# CF_DAC.net
KiCad netlist of a schematic drawn in Altium Designer
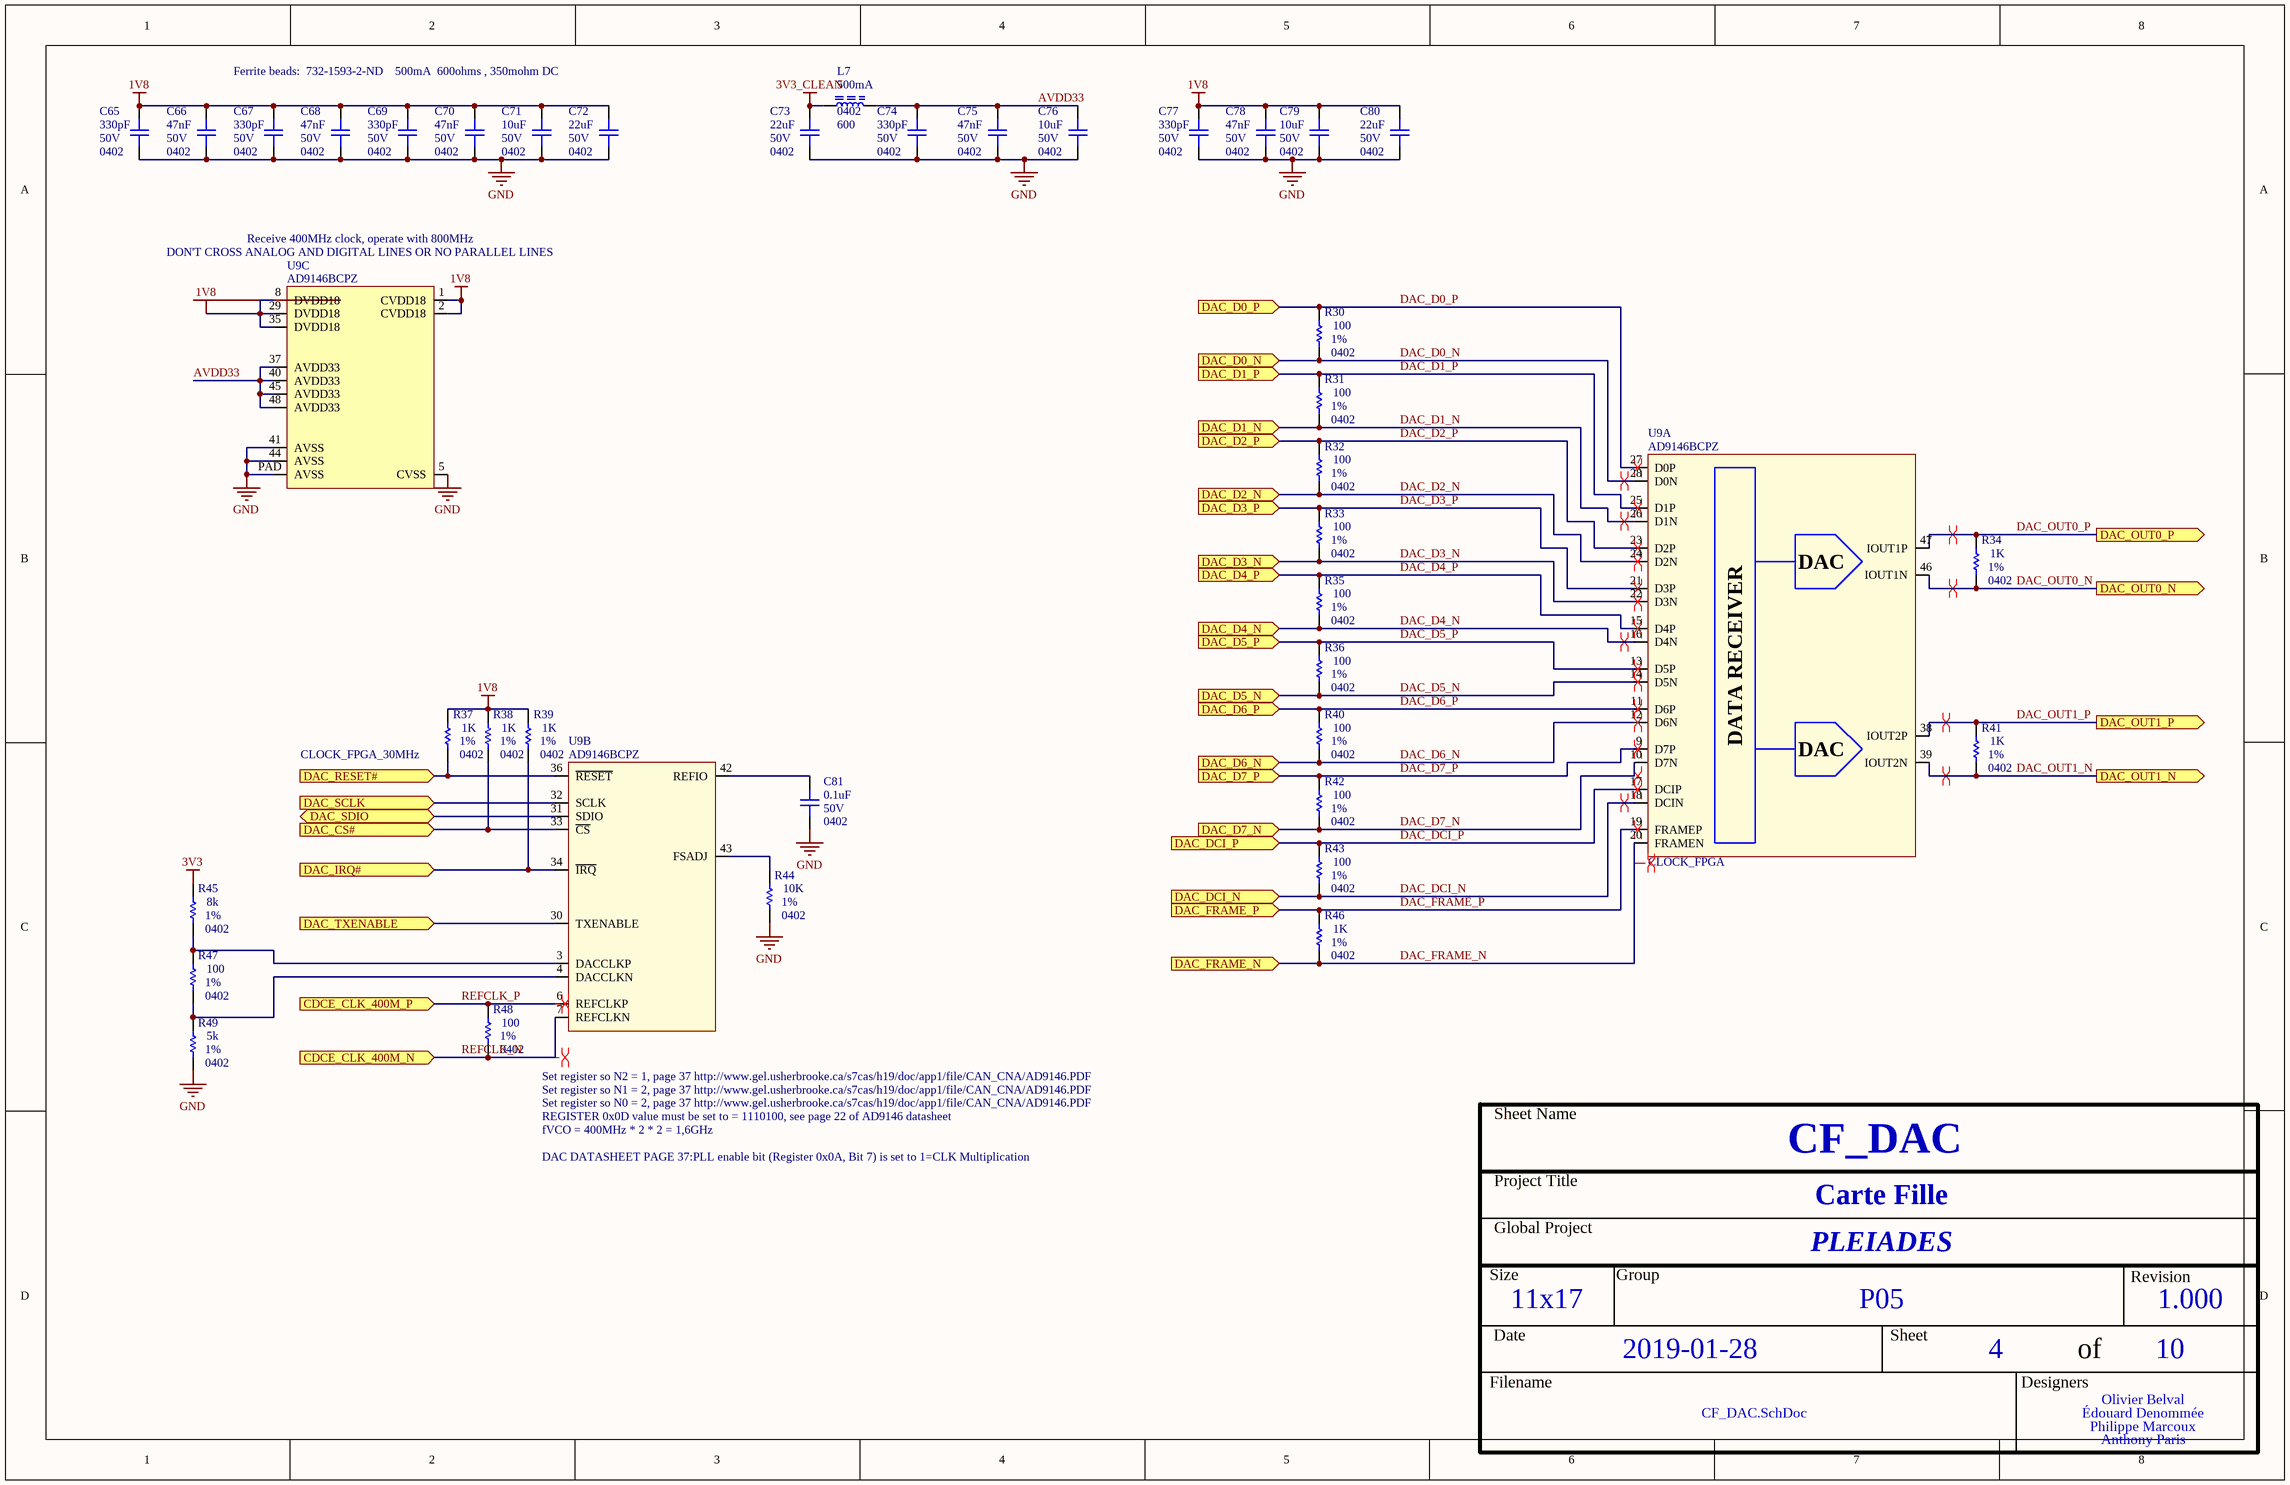
[diagram p0: CF_DAC.SchDoc]

(export (version "E")
  (design (tool "Eeschema 10.0.6"))
  (components
    (comp (ref "C65")
      (value "330pF")
      (footprint "CAP_0402")
      (description "CAP - 0402")
      (fields
        (field (name "VOLTAGE") "50V")
        (field (name "PACKAGE") "0402")
        (field (name "CREATEDBY") "Jonathan Bouchard")
      )
      (libsource (lib "S7CAS_Lib2019_REV1_00") (part "CAP - 0402"))
    )
    (comp (ref "C66")
      (value "47nF")
      (footprint "CAP_0402")
      (description "CAP - 0402")
      (fields
        (field (name "VOLTAGE") "50V")
        (field (name "PACKAGE") "0402")
        (field (name "CREATEDBY") "Jonathan Bouchard")
      )
      (libsource (lib "S7CAS_Lib2019_REV1_00") (part "CAP - 0402"))
    )
    (comp (ref "C67")
      (value "330pF")
      (footprint "CAP_0402")
      (description "CAP - 0402")
      (fields
        (field (name "VOLTAGE") "50V")
        (field (name "PACKAGE") "0402")
        (field (name "CREATEDBY") "Jonathan Bouchard")
      )
      (libsource (lib "S7CAS_Lib2019_REV1_00") (part "CAP - 0402"))
    )
    (comp (ref "C68")
      (value "47nF")
      (footprint "CAP_0402")
      (description "CAP - 0402")
      (fields
        (field (name "VOLTAGE") "50V")
        (field (name "PACKAGE") "0402")
        (field (name "CREATEDBY") "Jonathan Bouchard")
      )
      (libsource (lib "S7CAS_Lib2019_REV1_00") (part "CAP - 0402"))
    )
    (comp (ref "C69")
      (value "330pF")
      (footprint "CAP_0402")
      (description "CAP - 0402")
      (fields
        (field (name "VOLTAGE") "50V")
        (field (name "PACKAGE") "0402")
        (field (name "CREATEDBY") "Jonathan Bouchard")
      )
      (libsource (lib "S7CAS_Lib2019_REV1_00") (part "CAP - 0402"))
    )
    (comp (ref "C70")
      (value "47nF")
      (footprint "CAP_0402")
      (description "CAP - 0402")
      (fields
        (field (name "VOLTAGE") "50V")
        (field (name "PACKAGE") "0402")
        (field (name "CREATEDBY") "Jonathan Bouchard")
      )
      (libsource (lib "S7CAS_Lib2019_REV1_00") (part "CAP - 0402"))
    )
    (comp (ref "C71")
      (value "10uF")
      (footprint "CAP_0402")
      (description "CAP - 0402")
      (fields
        (field (name "VOLTAGE") "50V")
        (field (name "PACKAGE") "0402")
        (field (name "CREATEDBY") "Jonathan Bouchard")
      )
      (libsource (lib "S7CAS_Lib2019_REV1_00") (part "CAP - 0402"))
    )
    (comp (ref "C72")
      (value "22uF")
      (footprint "CAP_0402")
      (description "CAP - 0402")
      (fields
        (field (name "VOLTAGE") "50V")
        (field (name "PACKAGE") "0402")
        (field (name "CREATEDBY") "Jonathan Bouchard")
      )
      (libsource (lib "S7CAS_Lib2019_REV1_00") (part "CAP - 0402"))
    )
    (comp (ref "C73")
      (value "22uF")
      (footprint "CAP_0402")
      (description "CAP - 0402")
      (fields
        (field (name "VOLTAGE") "50V")
        (field (name "PACKAGE") "0402")
        (field (name "CREATEDBY") "Jonathan Bouchard")
      )
      (libsource (lib "S7CAS_Lib2019_REV1_00") (part "CAP - 0402"))
    )
    (comp (ref "C74")
      (value "330pF")
      (footprint "CAP_0402")
      (description "CAP - 0402")
      (fields
        (field (name "VOLTAGE") "50V")
        (field (name "PACKAGE") "0402")
        (field (name "CREATEDBY") "Jonathan Bouchard")
      )
      (libsource (lib "S7CAS_Lib2019_REV1_00") (part "CAP - 0402"))
    )
    (comp (ref "C75")
      (value "47nF")
      (footprint "CAP_0402")
      (description "CAP - 0402")
      (fields
        (field (name "VOLTAGE") "50V")
        (field (name "PACKAGE") "0402")
        (field (name "CREATEDBY") "Jonathan Bouchard")
      )
      (libsource (lib "S7CAS_Lib2019_REV1_00") (part "CAP - 0402"))
    )
    (comp (ref "C76")
      (value "10uF")
      (footprint "CAP_0402")
      (description "CAP - 0402")
      (fields
        (field (name "VOLTAGE") "50V")
        (field (name "PACKAGE") "0402")
        (field (name "CREATEDBY") "Jonathan Bouchard")
      )
      (libsource (lib "S7CAS_Lib2019_REV1_00") (part "CAP - 0402"))
    )
    (comp (ref "C77")
      (value "330pF")
      (footprint "CAP_0402")
      (description "CAP - 0402")
      (fields
        (field (name "VOLTAGE") "50V")
        (field (name "PACKAGE") "0402")
        (field (name "CREATEDBY") "Jonathan Bouchard")
      )
      (libsource (lib "S7CAS_Lib2019_REV1_00") (part "CAP - 0402"))
    )
    (comp (ref "C78")
      (value "47nF")
      (footprint "CAP_0402")
      (description "CAP - 0402")
      (fields
        (field (name "VOLTAGE") "50V")
        (field (name "PACKAGE") "0402")
        (field (name "CREATEDBY") "Jonathan Bouchard")
      )
      (libsource (lib "S7CAS_Lib2019_REV1_00") (part "CAP - 0402"))
    )
    (comp (ref "C79")
      (value "10uF")
      (footprint "CAP_0402")
      (description "CAP - 0402")
      (fields
        (field (name "VOLTAGE") "50V")
        (field (name "PACKAGE") "0402")
        (field (name "CREATEDBY") "Jonathan Bouchard")
      )
      (libsource (lib "S7CAS_Lib2019_REV1_00") (part "CAP - 0402"))
    )
    (comp (ref "C80")
      (value "22uF")
      (footprint "CAP_0402")
      (description "CAP - 0402")
      (fields
        (field (name "VOLTAGE") "50V")
        (field (name "PACKAGE") "0402")
        (field (name "CREATEDBY") "Jonathan Bouchard")
      )
      (libsource (lib "S7CAS_Lib2019_REV1_00") (part "CAP - 0402"))
    )
    (comp (ref "C81")
      (value "0.1uF")
      (footprint "CAP_0402")
      (description "CAP - 0402")
      (fields
        (field (name "VOLTAGE") "50V")
        (field (name "PACKAGE") "0402")
        (field (name "CREATEDBY") "Jonathan Bouchard")
      )
      (libsource (lib "S7CAS_Lib2019_REV1_00") (part "CAP - 0402"))
    )
    (comp (ref "L7")
      (value "600")
      (footprint "FER_0402")
      (description "FER - 0402")
      (fields
        (field (name "CURRENT") "500mA")
        (field (name "PACKAGE") "0402")
        (field (name "CREATEDBY") "Jonathan Bouchard")
      )
      (libsource (lib "S7CAS_Lib2019_REV1_00") (part "FER - 0402"))
    )
    (comp (ref "R30")
      (value "100")
      (footprint "RES_0402")
      (description "RES - 0402")
      (fields
        (field (name "VOLTAGE") "50V")
        (field (name "POWER") "1/16W")
        (field (name "PACKAGE") "0402")
        (field (name "PRECISION") "1%")
        (field (name "CREATEDBY") "Jonathan Bouchard")
      )
      (libsource (lib "S7CAS_Lib2019_REV1_00") (part "RES - 0402"))
    )
    (comp (ref "R31")
      (value "100")
      (footprint "RES_0402")
      (description "RES - 0402")
      (fields
        (field (name "VOLTAGE") "50V")
        (field (name "POWER") "1/16W")
        (field (name "PACKAGE") "0402")
        (field (name "PRECISION") "1%")
        (field (name "CREATEDBY") "Jonathan Bouchard")
      )
      (libsource (lib "S7CAS_Lib2019_REV1_00") (part "RES - 0402"))
    )
    (comp (ref "R32")
      (value "100")
      (footprint "RES_0402")
      (description "RES - 0402")
      (fields
        (field (name "VOLTAGE") "50V")
        (field (name "POWER") "1/16W")
        (field (name "PACKAGE") "0402")
        (field (name "PRECISION") "1%")
        (field (name "CREATEDBY") "Jonathan Bouchard")
      )
      (libsource (lib "S7CAS_Lib2019_REV1_00") (part "RES - 0402"))
    )
    (comp (ref "R33")
      (value "100")
      (footprint "RES_0402")
      (description "RES - 0402")
      (fields
        (field (name "VOLTAGE") "50V")
        (field (name "POWER") "1/16W")
        (field (name "PACKAGE") "0402")
        (field (name "PRECISION") "1%")
        (field (name "CREATEDBY") "Jonathan Bouchard")
      )
      (libsource (lib "S7CAS_Lib2019_REV1_00") (part "RES - 0402"))
    )
    (comp (ref "R34")
      (value "1K")
      (footprint "RES_0402")
      (description "RES - 0402")
      (fields
        (field (name "VOLTAGE") "50V")
        (field (name "POWER") "1/16W")
        (field (name "PACKAGE") "0402")
        (field (name "PRECISION") "1%")
        (field (name "CREATEDBY") "Jonathan Bouchard")
      )
      (libsource (lib "S7CAS_Lib2019_REV1_00") (part "RES - 0402"))
    )
    (comp (ref "R35")
      (value "100")
      (footprint "RES_0402")
      (description "RES - 0402")
      (fields
        (field (name "VOLTAGE") "50V")
        (field (name "POWER") "1/16W")
        (field (name "PACKAGE") "0402")
        (field (name "PRECISION") "1%")
        (field (name "CREATEDBY") "Jonathan Bouchard")
      )
      (libsource (lib "S7CAS_Lib2019_REV1_00") (part "RES - 0402"))
    )
    (comp (ref "R36")
      (value "100")
      (footprint "RES_0402")
      (description "RES - 0402")
      (fields
        (field (name "VOLTAGE") "50V")
        (field (name "POWER") "1/16W")
        (field (name "PACKAGE") "0402")
        (field (name "PRECISION") "1%")
        (field (name "CREATEDBY") "Jonathan Bouchard")
      )
      (libsource (lib "S7CAS_Lib2019_REV1_00") (part "RES - 0402"))
    )
    (comp (ref "R37")
      (value "1K")
      (footprint "RES_0402")
      (description "RES - 0402")
      (fields
        (field (name "VOLTAGE") "50V")
        (field (name "POWER") "1/16W")
        (field (name "PACKAGE") "0402")
        (field (name "PRECISION") "1%")
        (field (name "CREATEDBY") "Jonathan Bouchard")
      )
      (libsource (lib "S7CAS_Lib2019_REV1_00") (part "RES - 0402"))
    )
    (comp (ref "R38")
      (value "1K")
      (footprint "RES_0402")
      (description "RES - 0402")
      (fields
        (field (name "VOLTAGE") "50V")
        (field (name "POWER") "1/16W")
        (field (name "PACKAGE") "0402")
        (field (name "PRECISION") "1%")
        (field (name "CREATEDBY") "Jonathan Bouchard")
      )
      (libsource (lib "S7CAS_Lib2019_REV1_00") (part "RES - 0402"))
    )
    (comp (ref "R39")
      (value "1K")
      (footprint "RES_0402")
      (description "RES - 0402")
      (fields
        (field (name "VOLTAGE") "50V")
        (field (name "POWER") "1/16W")
        (field (name "PACKAGE") "0402")
        (field (name "PRECISION") "1%")
        (field (name "CREATEDBY") "Jonathan Bouchard")
      )
      (libsource (lib "S7CAS_Lib2019_REV1_00") (part "RES - 0402"))
    )
    (comp (ref "R40")
      (value "100")
      (footprint "RES_0402")
      (description "RES - 0402")
      (fields
        (field (name "VOLTAGE") "50V")
        (field (name "POWER") "1/16W")
        (field (name "PACKAGE") "0402")
        (field (name "PRECISION") "1%")
        (field (name "CREATEDBY") "Jonathan Bouchard")
      )
      (libsource (lib "S7CAS_Lib2019_REV1_00") (part "RES - 0402"))
    )
    (comp (ref "R41")
      (value "1K")
      (footprint "RES_0402")
      (description "RES - 0402")
      (fields
        (field (name "VOLTAGE") "50V")
        (field (name "POWER") "1/16W")
        (field (name "PACKAGE") "0402")
        (field (name "PRECISION") "1%")
        (field (name "CREATEDBY") "Jonathan Bouchard")
      )
      (libsource (lib "S7CAS_Lib2019_REV1_00") (part "RES - 0402"))
    )
    (comp (ref "R42")
      (value "100")
      (footprint "RES_0402")
      (description "RES - 0402")
      (fields
        (field (name "VOLTAGE") "50V")
        (field (name "POWER") "1/16W")
        (field (name "PACKAGE") "0402")
        (field (name "PRECISION") "1%")
        (field (name "CREATEDBY") "Jonathan Bouchard")
      )
      (libsource (lib "S7CAS_Lib2019_REV1_00") (part "RES - 0402"))
    )
    (comp (ref "R43")
      (value "100")
      (footprint "RES_0402")
      (description "RES - 0402")
      (fields
        (field (name "VOLTAGE") "50V")
        (field (name "POWER") "1/16W")
        (field (name "PACKAGE") "0402")
        (field (name "PRECISION") "1%")
        (field (name "CREATEDBY") "Jonathan Bouchard")
      )
      (libsource (lib "S7CAS_Lib2019_REV1_00") (part "RES - 0402"))
    )
    (comp (ref "R44")
      (value "10K")
      (footprint "RES_0402")
      (description "RES - 0402")
      (fields
        (field (name "VOLTAGE") "50V")
        (field (name "POWER") "1/16W")
        (field (name "PACKAGE") "0402")
        (field (name "PRECISION") "1%")
        (field (name "CREATEDBY") "Jonathan Bouchard")
      )
      (libsource (lib "S7CAS_Lib2019_REV1_00") (part "RES - 0402"))
    )
    (comp (ref "R45")
      (value "8k")
      (footprint "RES_0402")
      (description "RES - 0402")
      (fields
        (field (name "VOLTAGE") "50V")
        (field (name "POWER") "1/16W")
        (field (name "PACKAGE") "0402")
        (field (name "PRECISION") "1%")
        (field (name "CREATEDBY") "Jonathan Bouchard")
      )
      (libsource (lib "S7CAS_Lib2019_REV1_00") (part "RES - 0402"))
    )
    (comp (ref "R46")
      (value "1K")
      (footprint "RES_0402")
      (description "RES - 0402")
      (fields
        (field (name "VOLTAGE") "50V")
        (field (name "POWER") "1/16W")
        (field (name "PACKAGE") "0402")
        (field (name "PRECISION") "1%")
        (field (name "CREATEDBY") "Jonathan Bouchard")
      )
      (libsource (lib "S7CAS_Lib2019_REV1_00") (part "RES - 0402"))
    )
    (comp (ref "R47")
      (value "100")
      (footprint "RES_0402")
      (description "RES - 0402")
      (fields
        (field (name "VOLTAGE") "50V")
        (field (name "POWER") "1/16W")
        (field (name "PACKAGE") "0402")
        (field (name "PRECISION") "1%")
        (field (name "CREATEDBY") "Jonathan Bouchard")
      )
      (libsource (lib "S7CAS_Lib2019_REV1_00") (part "RES - 0402"))
    )
    (comp (ref "R48")
      (value "100")
      (footprint "RES_0402")
      (description "RES - 0402")
      (fields
        (field (name "VOLTAGE") "50V")
        (field (name "POWER") "1/16W")
        (field (name "PACKAGE") "0402")
        (field (name "PRECISION") "1%")
        (field (name "CREATEDBY") "Jonathan Bouchard")
      )
      (libsource (lib "S7CAS_Lib2019_REV1_00") (part "RES - 0402"))
    )
    (comp (ref "R49")
      (value "5k")
      (footprint "RES_0402")
      (description "RES - 0402")
      (fields
        (field (name "VOLTAGE") "50V")
        (field (name "POWER") "1/16W")
        (field (name "PACKAGE") "0402")
        (field (name "PRECISION") "1%")
        (field (name "CREATEDBY") "Jonathan Bouchard")
      )
      (libsource (lib "S7CAS_Lib2019_REV1_00") (part "RES - 0402"))
    )
    (comp (ref "U9")
      (value "AD9146BCPZ")
      (footprint "DAC_AD9146BCPZ")
      (description "DAC - 16BIT SRL HIGH SPEED - QFN-48")
      (fields
        (field (name "VOLTAGE") "3.13 V ~ 3.47 V / 1.71 V ~ 1.89 V")
        (field (name "MFG") "Analog Devices Inc.")
        (field (name "CREATEDBY") "Jonathan Bouchard")
      )
      (libsource (lib "S7CAS_Lib2019_REV1_00") (part "DAC_AD9146BCPZ"))
    )
  )
  (nets
    (net (code "1") (name "/AVDD33") (class "Default")
      (node (ref "C74") (pin "2") (pinfunction "2_2") (pintype "passive"))
      (node (ref "C75") (pin "2") (pinfunction "2_2") (pintype "passive"))
      (node (ref "C76") (pin "2") (pinfunction "2_2") (pintype "passive"))
      (node (ref "L7") (pin "1") (pinfunction "1_1") (pintype "passive"))
      (node (ref "U9") (pin "37") (pinfunction "AVDD33_37") (pintype "passive"))
      (node (ref "U9") (pin "40") (pinfunction "AVDD33_40") (pintype "passive"))
      (node (ref "U9") (pin "45") (pinfunction "AVDD33_45") (pintype "passive"))
      (node (ref "U9") (pin "48") (pinfunction "AVDD33_48") (pintype "passive"))
    )
    (net (code "2") (name "/DAC_CS#") (class "Default")
      (node (ref "R38") (pin "1") (pinfunction "1_1") (pintype "passive"))
      (node (ref "U9") (pin "33") (pinfunction "~{CS}_33") (pintype "passive"))
    )
    (net (code "3") (name "/DAC_D0_N") (class "Default")
      (node (ref "R30") (pin "1") (pinfunction "1_1") (pintype "passive"))
      (node (ref "U9") (pin "28") (pinfunction "D0N_28") (pintype "passive"))
    )
    (net (code "4") (name "/DAC_D0_P") (class "Default")
      (node (ref "R30") (pin "2") (pinfunction "2_2") (pintype "passive"))
      (node (ref "U9") (pin "27") (pinfunction "D0P_27") (pintype "passive"))
    )
    (net (code "5") (name "/DAC_D1_N") (class "Default")
      (node (ref "R31") (pin "1") (pinfunction "1_1") (pintype "passive"))
      (node (ref "U9") (pin "26") (pinfunction "D1N_26") (pintype "passive"))
    )
    (net (code "6") (name "/DAC_D1_P") (class "Default")
      (node (ref "R31") (pin "2") (pinfunction "2_2") (pintype "passive"))
      (node (ref "U9") (pin "25") (pinfunction "D1P_25") (pintype "passive"))
    )
    (net (code "7") (name "/DAC_D2_N") (class "Default")
      (node (ref "R32") (pin "1") (pinfunction "1_1") (pintype "passive"))
      (node (ref "U9") (pin "24") (pinfunction "D2N_24") (pintype "passive"))
    )
    (net (code "8") (name "/DAC_D2_P") (class "Default")
      (node (ref "R32") (pin "2") (pinfunction "2_2") (pintype "passive"))
      (node (ref "U9") (pin "23") (pinfunction "D2P_23") (pintype "passive"))
    )
    (net (code "9") (name "/DAC_D3_N") (class "Default")
      (node (ref "R33") (pin "1") (pinfunction "1_1") (pintype "passive"))
      (node (ref "U9") (pin "22") (pinfunction "D3N_22") (pintype "passive"))
    )
    (net (code "10") (name "/DAC_D3_P") (class "Default")
      (node (ref "R33") (pin "2") (pinfunction "2_2") (pintype "passive"))
      (node (ref "U9") (pin "21") (pinfunction "D3P_21") (pintype "passive"))
    )
    (net (code "11") (name "/DAC_D4_N") (class "Default")
      (node (ref "R35") (pin "1") (pinfunction "1_1") (pintype "passive"))
      (node (ref "U9") (pin "16") (pinfunction "D4N_16") (pintype "passive"))
    )
    (net (code "12") (name "/DAC_D4_P") (class "Default")
      (node (ref "R35") (pin "2") (pinfunction "2_2") (pintype "passive"))
      (node (ref "U9") (pin "15") (pinfunction "D4P_15") (pintype "passive"))
    )
    (net (code "13") (name "/DAC_D5_N") (class "Default")
      (node (ref "R36") (pin "1") (pinfunction "1_1") (pintype "passive"))
      (node (ref "U9") (pin "14") (pinfunction "D5N_14") (pintype "passive"))
    )
    (net (code "14") (name "/DAC_D5_P") (class "Default")
      (node (ref "R36") (pin "2") (pinfunction "2_2") (pintype "passive"))
      (node (ref "U9") (pin "13") (pinfunction "D5P_13") (pintype "passive"))
    )
    (net (code "15") (name "/DAC_D6_N") (class "Default")
      (node (ref "R40") (pin "1") (pinfunction "1_1") (pintype "passive"))
      (node (ref "U9") (pin "12") (pinfunction "D6N_12") (pintype "passive"))
    )
    (net (code "16") (name "/DAC_D6_P") (class "Default")
      (node (ref "R40") (pin "2") (pinfunction "2_2") (pintype "passive"))
      (node (ref "U9") (pin "11") (pinfunction "D6P_11") (pintype "passive"))
    )
    (net (code "17") (name "/DAC_D7_N") (class "Default")
      (node (ref "R42") (pin "1") (pinfunction "1_1") (pintype "passive"))
      (node (ref "U9") (pin "10") (pinfunction "D7N_10") (pintype "passive"))
    )
    (net (code "18") (name "/DAC_D7_P") (class "Default")
      (node (ref "R42") (pin "2") (pinfunction "2_2") (pintype "passive"))
      (node (ref "U9") (pin "9") (pinfunction "D7P_9") (pintype "passive"))
    )
    (net (code "19") (name "/DAC_DCI_N") (class "Default")
      (node (ref "R43") (pin "1") (pinfunction "1_1") (pintype "passive"))
      (node (ref "U9") (pin "18") (pinfunction "DCIN_18") (pintype "passive"))
    )
    (net (code "20") (name "/DAC_DCI_P") (class "Default")
      (node (ref "R43") (pin "2") (pinfunction "2_2") (pintype "passive"))
      (node (ref "U9") (pin "17") (pinfunction "DCIP_17") (pintype "passive"))
    )
    (net (code "21") (name "/DAC_FRAME_N") (class "Default")
      (node (ref "R46") (pin "1") (pinfunction "1_1") (pintype "passive"))
      (node (ref "U9") (pin "20") (pinfunction "FRAMEN_20") (pintype "passive"))
    )
    (net (code "22") (name "/DAC_FRAME_P") (class "Default")
      (node (ref "R46") (pin "2") (pinfunction "2_2") (pintype "passive"))
      (node (ref "U9") (pin "19") (pinfunction "FRAMEP_19") (pintype "passive"))
    )
    (net (code "23") (name "/DAC_IRQ#") (class "Default")
      (node (ref "R39") (pin "1") (pinfunction "1_1") (pintype "passive"))
      (node (ref "U9") (pin "34") (pinfunction "~{IRQ}_34") (pintype "passive"))
    )
    (net (code "24") (name "/DAC_OUT0_N") (class "Default")
      (node (ref "R34") (pin "1") (pinfunction "1_1") (pintype "passive"))
      (node (ref "U9") (pin "46") (pinfunction "IOUT1N_46") (pintype "passive"))
    )
    (net (code "25") (name "/DAC_OUT0_P") (class "Default")
      (node (ref "R34") (pin "2") (pinfunction "2_2") (pintype "passive"))
      (node (ref "U9") (pin "47") (pinfunction "IOUT1P_47") (pintype "passive"))
    )
    (net (code "26") (name "/DAC_OUT1_N") (class "Default")
      (node (ref "R41") (pin "1") (pinfunction "1_1") (pintype "passive"))
      (node (ref "U9") (pin "39") (pinfunction "IOUT2N_39") (pintype "passive"))
    )
    (net (code "27") (name "/DAC_OUT1_P") (class "Default")
      (node (ref "R41") (pin "2") (pinfunction "2_2") (pintype "passive"))
      (node (ref "U9") (pin "38") (pinfunction "IOUT2P_38") (pintype "passive"))
    )
    (net (code "28") (name "/DAC_RESET#") (class "Default")
      (node (ref "R37") (pin "1") (pinfunction "1_1") (pintype "passive"))
      (node (ref "U9") (pin "36") (pinfunction "~{RESET}_36") (pintype "passive"))
    )
    (net (code "29") (name "/DAC_SCLK") (class "Default")
      (node (ref "U9") (pin "32") (pinfunction "SCLK_32") (pintype "passive"))
    )
    (net (code "30") (name "/DAC_SDIO") (class "Default")
      (node (ref "U9") (pin "31") (pinfunction "SDIO_31") (pintype "passive"))
    )
    (net (code "31") (name "/DAC_TXENABLE") (class "Default")
      (node (ref "U9") (pin "30") (pinfunction "TXENABLE_30") (pintype "passive"))
    )
    (net (code "32") (name "/REFCLK_N") (class "Default")
      (node (ref "R48") (pin "1") (pinfunction "1_1") (pintype "passive"))
      (node (ref "U9") (pin "7") (pinfunction "REFCLKN_7") (pintype "passive"))
    )
    (net (code "33") (name "/REFCLK_P") (class "Default")
      (node (ref "R48") (pin "2") (pinfunction "2_2") (pintype "passive"))
      (node (ref "U9") (pin "6") (pinfunction "REFCLKP_6") (pintype "passive"))
    )
    (net (code "34") (name "1V8") (class "Default")
      (node (ref "C65") (pin "2") (pinfunction "2_2") (pintype "passive"))
      (node (ref "C66") (pin "2") (pinfunction "2_2") (pintype "passive"))
      (node (ref "C67") (pin "2") (pinfunction "2_2") (pintype "passive"))
      (node (ref "C68") (pin "2") (pinfunction "2_2") (pintype "passive"))
      (node (ref "C69") (pin "2") (pinfunction "2_2") (pintype "passive"))
      (node (ref "C70") (pin "2") (pinfunction "2_2") (pintype "passive"))
      (node (ref "C71") (pin "2") (pinfunction "2_2") (pintype "passive"))
      (node (ref "C72") (pin "2") (pinfunction "2_2") (pintype "passive"))
      (node (ref "C77") (pin "2") (pinfunction "2_2") (pintype "passive"))
      (node (ref "C78") (pin "2") (pinfunction "2_2") (pintype "passive"))
      (node (ref "C79") (pin "2") (pinfunction "2_2") (pintype "passive"))
      (node (ref "C80") (pin "2") (pinfunction "2_2") (pintype "passive"))
      (node (ref "R37") (pin "2") (pinfunction "2_2") (pintype "passive"))
      (node (ref "R38") (pin "2") (pinfunction "2_2") (pintype "passive"))
      (node (ref "R39") (pin "2") (pinfunction "2_2") (pintype "passive"))
      (node (ref "U9") (pin "1") (pinfunction "CVDD18_1") (pintype "passive"))
      (node (ref "U9") (pin "2") (pinfunction "CVDD18_2") (pintype "passive"))
      (node (ref "U9") (pin "29") (pinfunction "DVDD18_29") (pintype "passive"))
      (node (ref "U9") (pin "35") (pinfunction "DVDD18_35") (pintype "passive"))
      (node (ref "U9") (pin "8") (pinfunction "DVDD18_8") (pintype "passive"))
    )
    (net (code "35") (name "3V3") (class "Default")
      (node (ref "R45") (pin "2") (pinfunction "2_2") (pintype "passive"))
    )
    (net (code "36") (name "3V3_CLEAN") (class "Default")
      (node (ref "C73") (pin "2") (pinfunction "2_2") (pintype "passive"))
      (node (ref "L7") (pin "2") (pinfunction "2_2") (pintype "passive"))
    )
    (net (code "37") (name "GND") (class "Default")
      (node (ref "C65") (pin "1") (pinfunction "1_1") (pintype "passive"))
      (node (ref "C66") (pin "1") (pinfunction "1_1") (pintype "passive"))
      (node (ref "C67") (pin "1") (pinfunction "1_1") (pintype "passive"))
      (node (ref "C68") (pin "1") (pinfunction "1_1") (pintype "passive"))
      (node (ref "C69") (pin "1") (pinfunction "1_1") (pintype "passive"))
      (node (ref "C70") (pin "1") (pinfunction "1_1") (pintype "passive"))
      (node (ref "C71") (pin "1") (pinfunction "1_1") (pintype "passive"))
      (node (ref "C72") (pin "1") (pinfunction "1_1") (pintype "passive"))
      (node (ref "C73") (pin "1") (pinfunction "1_1") (pintype "passive"))
      (node (ref "C74") (pin "1") (pinfunction "1_1") (pintype "passive"))
      (node (ref "C75") (pin "1") (pinfunction "1_1") (pintype "passive"))
      (node (ref "C76") (pin "1") (pinfunction "1_1") (pintype "passive"))
      (node (ref "C77") (pin "1") (pinfunction "1_1") (pintype "passive"))
      (node (ref "C78") (pin "1") (pinfunction "1_1") (pintype "passive"))
      (node (ref "C79") (pin "1") (pinfunction "1_1") (pintype "passive"))
      (node (ref "C80") (pin "1") (pinfunction "1_1") (pintype "passive"))
      (node (ref "C81") (pin "1") (pinfunction "1_1") (pintype "passive"))
      (node (ref "R44") (pin "1") (pinfunction "1_1") (pintype "passive"))
      (node (ref "R49") (pin "1") (pinfunction "1_1") (pintype "passive"))
      (node (ref "U9") (pin "41") (pinfunction "AVSS_41") (pintype "passive"))
      (node (ref "U9") (pin "44") (pinfunction "AVSS_44") (pintype "passive"))
      (node (ref "U9") (pin "5") (pinfunction "CVSS_5") (pintype "passive"))
      (node (ref "U9") (pin "PAD") (pinfunction "AVSS_PAD") (pintype "passive"))
    )
    (net (code "38") (name "Net-(U9B-DACCLKN)") (class "Default")
      (node (ref "R47") (pin "1") (pinfunction "1_1") (pintype "passive"))
      (node (ref "R49") (pin "2") (pinfunction "2_2") (pintype "passive"))
      (node (ref "U9") (pin "4") (pinfunction "DACCLKN_4") (pintype "passive"))
    )
    (net (code "39") (name "Net-(U9B-DACCLKP)") (class "Default")
      (node (ref "R45") (pin "1") (pinfunction "1_1") (pintype "passive"))
      (node (ref "R47") (pin "2") (pinfunction "2_2") (pintype "passive"))
      (node (ref "U9") (pin "3") (pinfunction "DACCLKP_3") (pintype "passive"))
    )
    (net (code "40") (name "Net-(U9B-FSADJ)") (class "Default")
      (node (ref "R44") (pin "2") (pinfunction "2_2") (pintype "passive"))
      (node (ref "U9") (pin "43") (pinfunction "FSADJ_43") (pintype "passive"))
    )
    (net (code "41") (name "Net-(U9B-REFIO)") (class "Default")
      (node (ref "C81") (pin "2") (pinfunction "2_2") (pintype "passive"))
      (node (ref "U9") (pin "42") (pinfunction "REFIO_42") (pintype "passive"))
    )
  )
)
